# iot-gateway-usb-pd.net
KiCad netlist of a schematic drawn in EAGLE
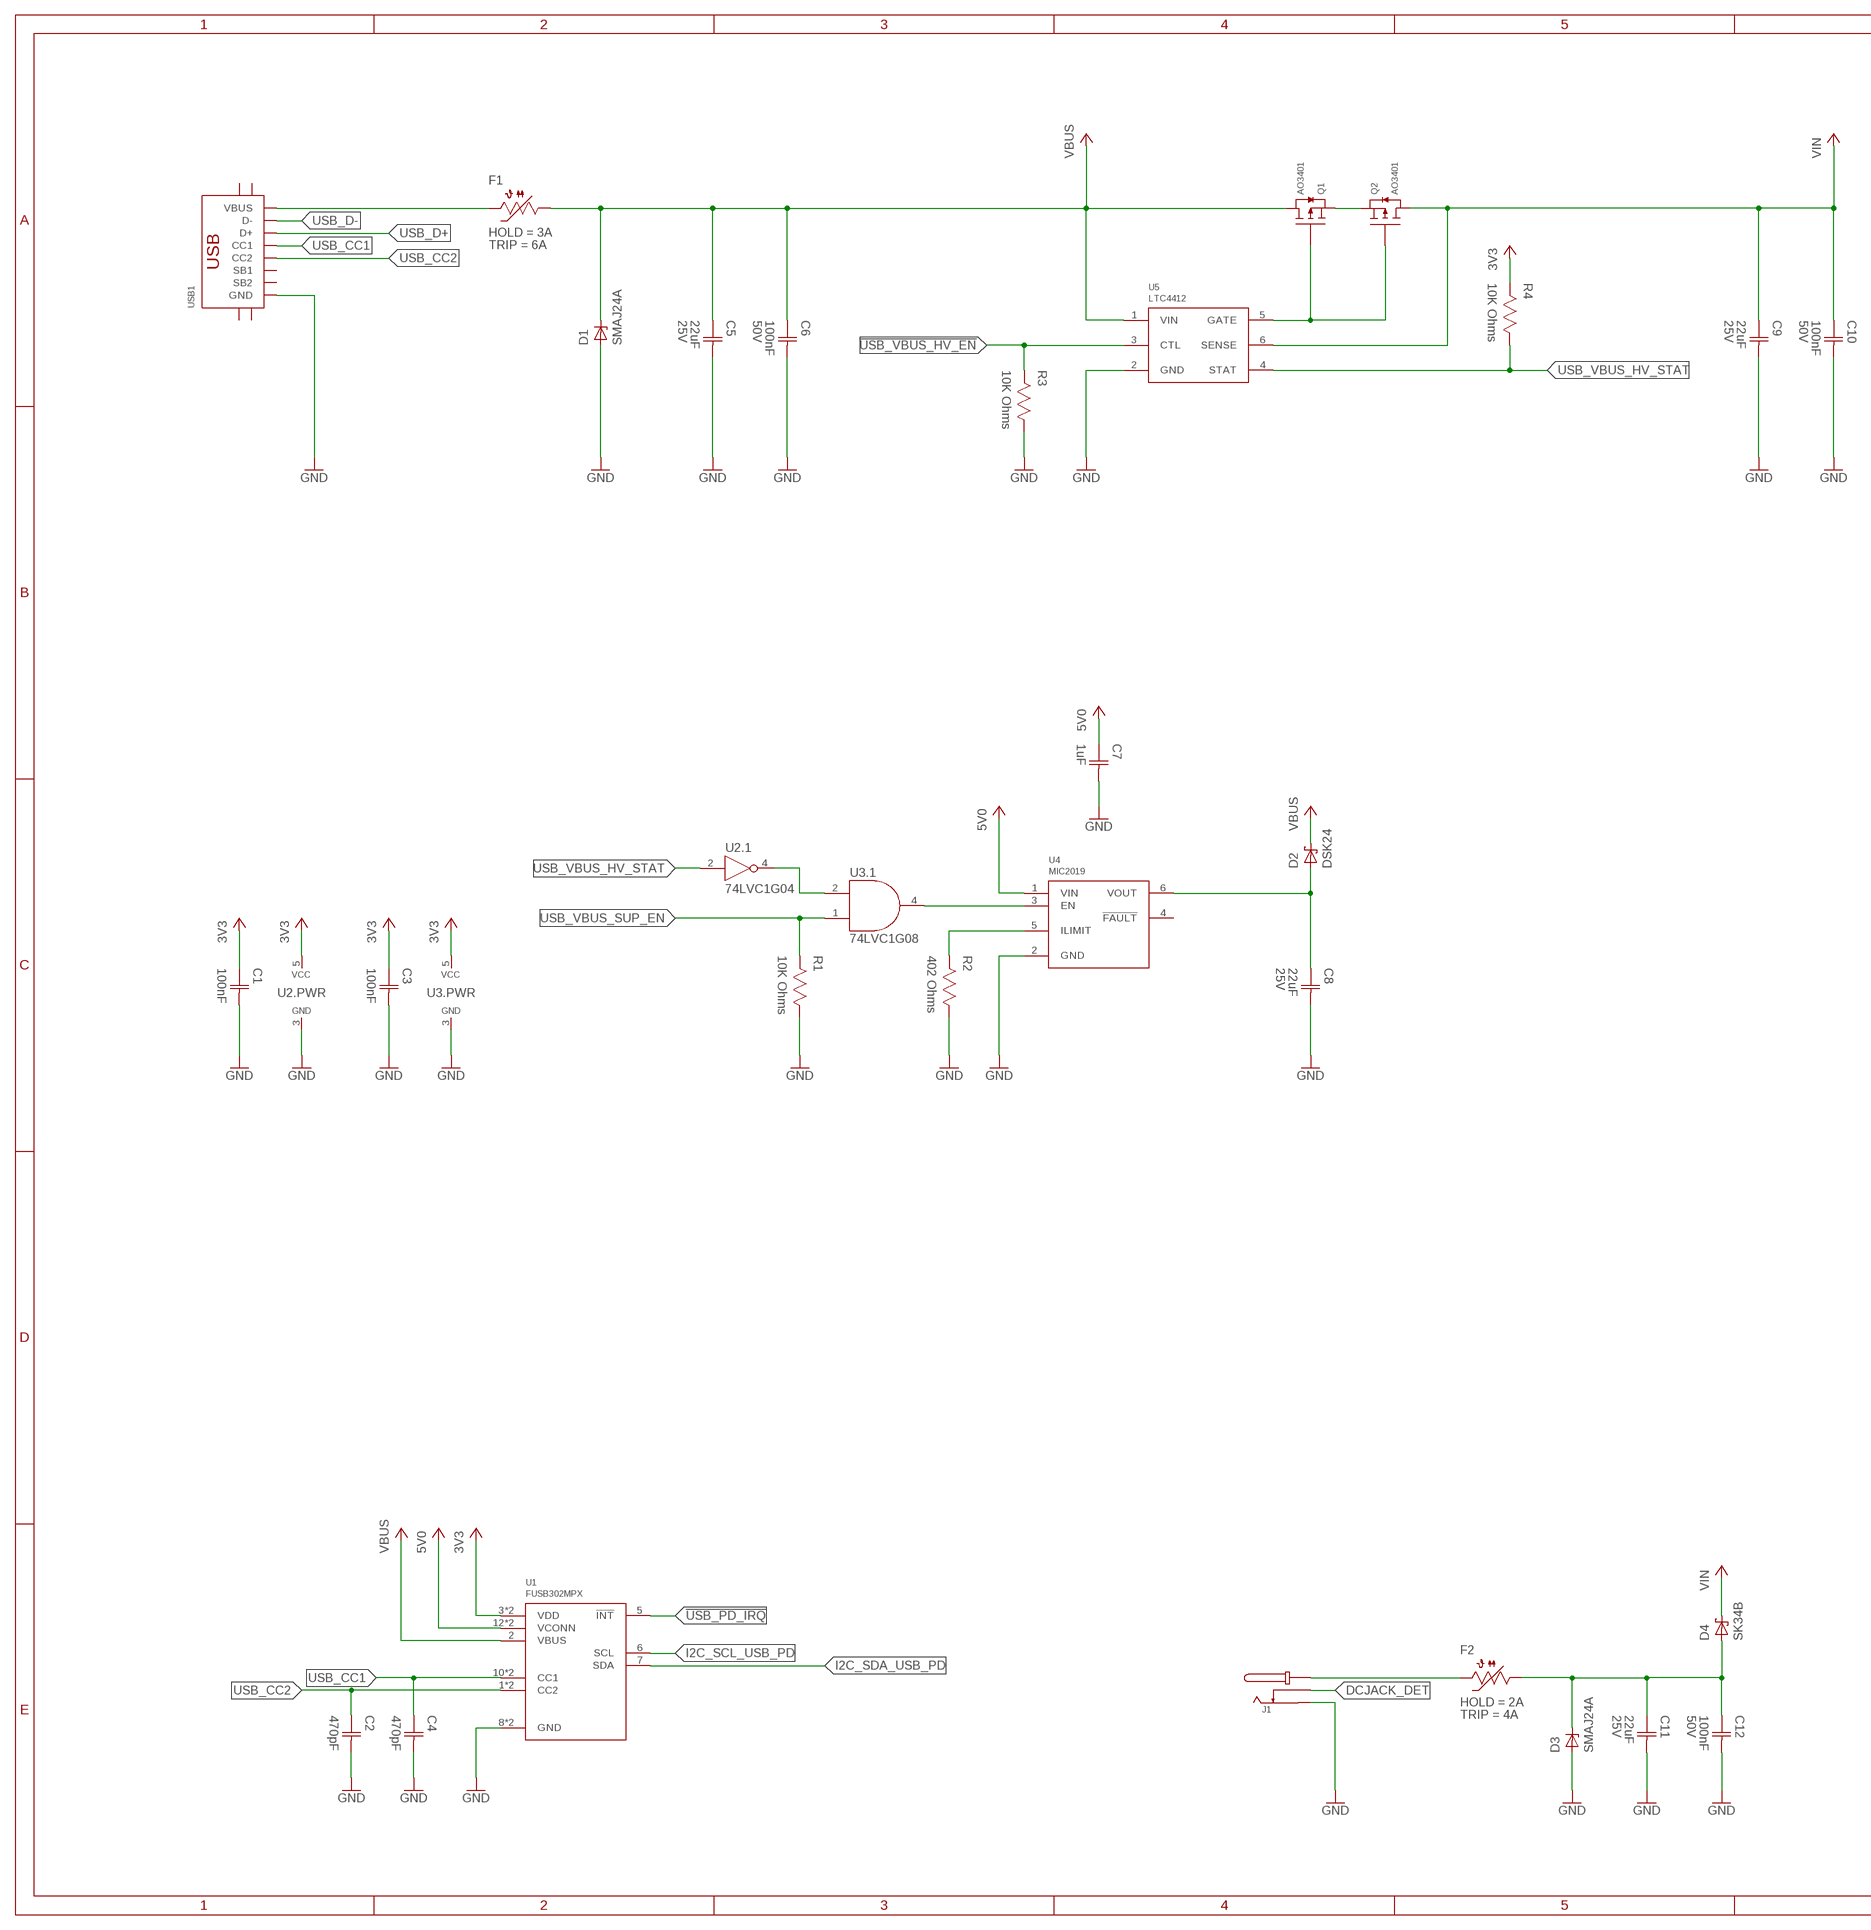
[diagram p0: schematic, sheet 1, part 1 of 2]
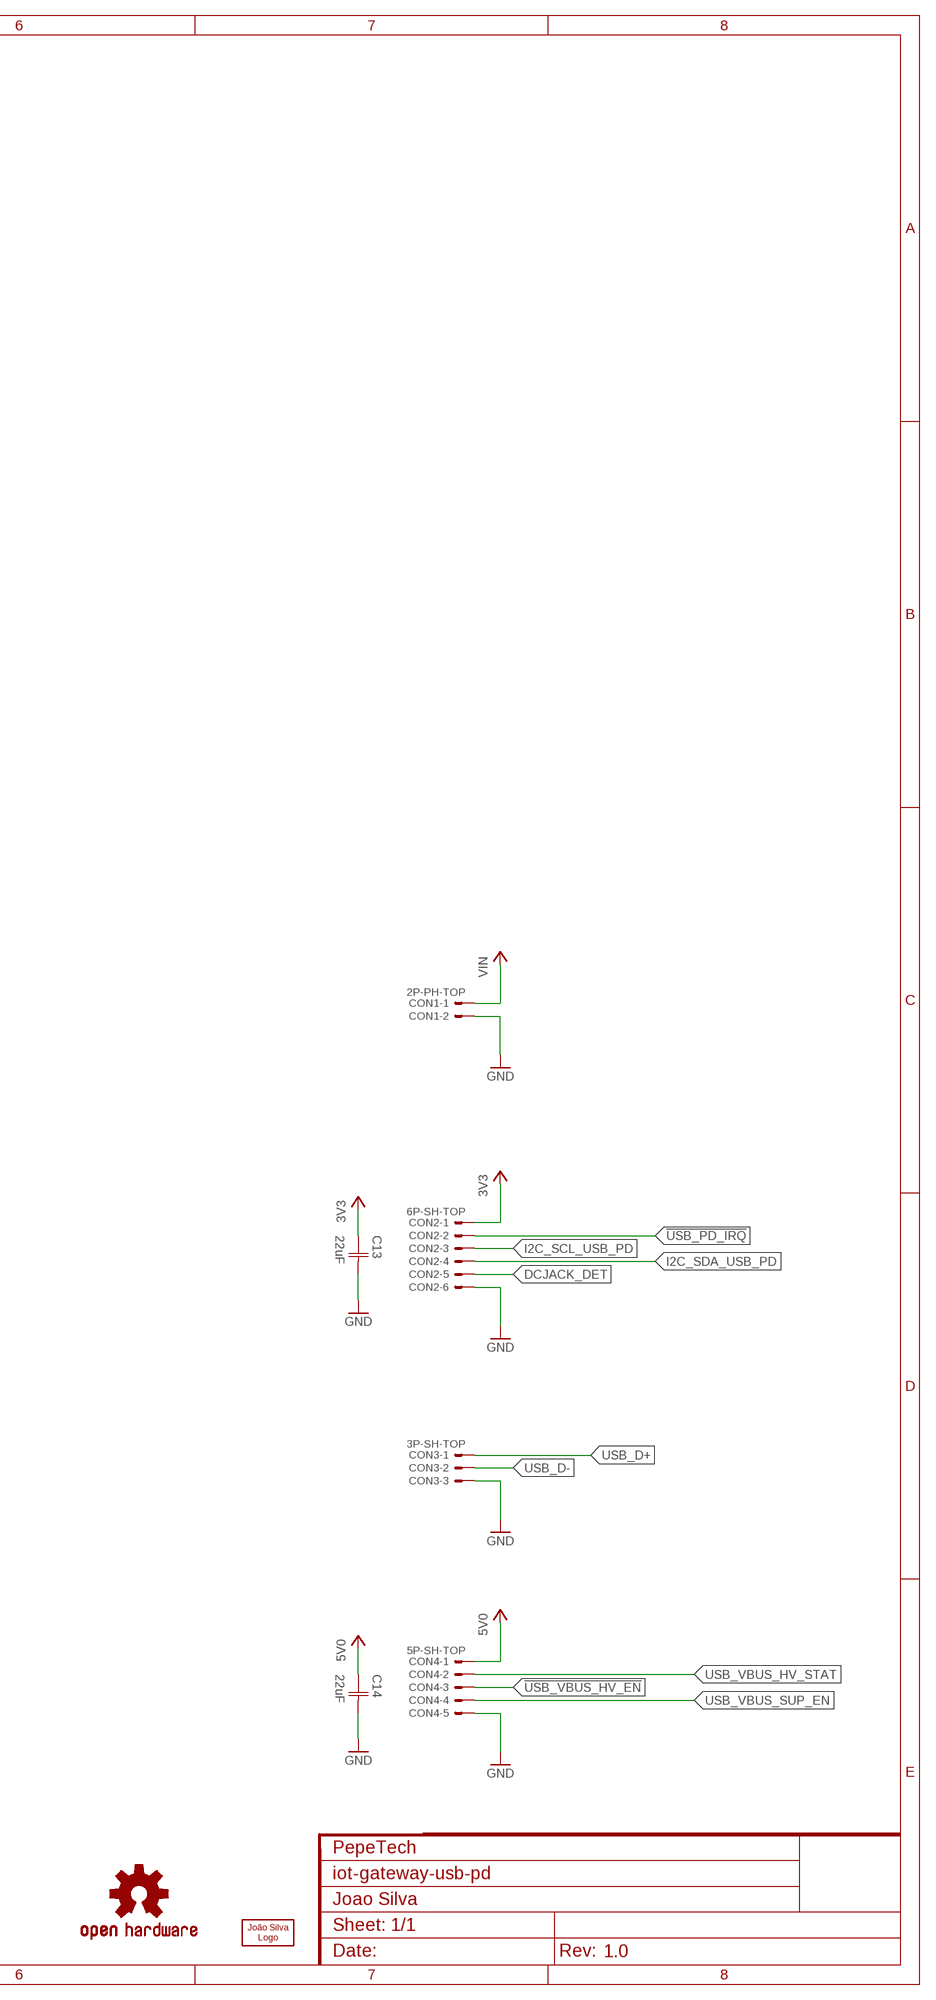
[diagram p1: schematic, sheet 1, part 2 of 2]

(export (version "E")
  (design (tool "Eeschema 10.0.6"))
  (components
    (comp (ref "C1")
      (value "100nF")
      (footprint "eagle-import:CAP0603")
      (libsource (lib "eagle-import") (part "CAPACITOR-0603"))
    )
    (comp (ref "C2")
      (value "470pF")
      (footprint "eagle-import:CAP0603")
      (libsource (lib "eagle-import") (part "CAPACITOR-0603"))
    )
    (comp (ref "C3")
      (value "100nF")
      (footprint "eagle-import:CAP0603")
      (libsource (lib "eagle-import") (part "CAPACITOR-0603"))
    )
    (comp (ref "C4")
      (value "470pF")
      (footprint "eagle-import:CAP0603")
      (libsource (lib "eagle-import") (part "CAPACITOR-0603"))
    )
    (comp (ref "C5")
      (value "22uF")
      (footprint "eagle-import:CAP1206")
      (fields (field (name "VOLTAGE") "25V"))
      (libsource (lib "eagle-import") (part "CAPACITOR-1206"))
    )
    (comp (ref "C6")
      (value "100nF")
      (footprint "eagle-import:CAP0603")
      (fields (field (name "VOLTAGE") "50V"))
      (libsource (lib "eagle-import") (part "CAPACITOR-0603"))
    )
    (comp (ref "C7")
      (value "1uF")
      (footprint "eagle-import:CAP0603")
      (libsource (lib "eagle-import") (part "CAPACITOR-0603"))
    )
    (comp (ref "C8")
      (value "22uF")
      (footprint "eagle-import:CAP1206")
      (fields (field (name "VOLTAGE") "25V"))
      (libsource (lib "eagle-import") (part "CAPACITOR-1206"))
    )
    (comp (ref "C9")
      (value "22uF")
      (footprint "eagle-import:CAP1206")
      (fields (field (name "VOLTAGE") "25V"))
      (libsource (lib "eagle-import") (part "CAPACITOR-1206"))
    )
    (comp (ref "C10")
      (value "100nF")
      (footprint "eagle-import:CAP0603")
      (fields (field (name "VOLTAGE") "50V"))
      (libsource (lib "eagle-import") (part "CAPACITOR-0603"))
    )
    (comp (ref "C11")
      (value "22uF")
      (footprint "eagle-import:CAP1206")
      (fields (field (name "VOLTAGE") "25V"))
      (libsource (lib "eagle-import") (part "CAPACITOR-1206"))
    )
    (comp (ref "C12")
      (value "100nF")
      (footprint "eagle-import:CAP0603")
      (fields (field (name "VOLTAGE") "50V"))
      (libsource (lib "eagle-import") (part "CAPACITOR-0603"))
    )
    (comp (ref "C13")
      (value "22uF")
      (footprint "eagle-import:CAP1206")
      (libsource (lib "eagle-import") (part "CAPACITOR-1206"))
    )
    (comp (ref "C14")
      (value "22uF")
      (footprint "eagle-import:CAP1206")
      (libsource (lib "eagle-import") (part "CAPACITOR-1206"))
    )
    (comp (ref "CON1")
      (value "2P-PH-TOP")
      (footprint "eagle-import:PH-02-TOP")
      (libsource (lib "eagle-import") (part "2P-PH-TOP"))
    )
    (comp (ref "CON2")
      (value "6P-SH-TOP")
      (footprint "eagle-import:SH-06-TOP")
      (libsource (lib "eagle-import") (part "6P-SH-TOP"))
    )
    (comp (ref "CON3")
      (value "3P-SH-TOP")
      (footprint "eagle-import:SH-03-TOP")
      (libsource (lib "eagle-import") (part "3P-SH-TOP"))
    )
    (comp (ref "CON4")
      (value "5P-SH-TOP")
      (footprint "eagle-import:SH-05-TOP")
      (libsource (lib "eagle-import") (part "5P-SH-TOP"))
    )
    (comp (ref "D1")
      (value "SMAJ24A")
      (footprint "eagle-import:DO214AC")
      (fields (field (name "MF") "Littelfuse"))
      (libsource (lib "eagle-import") (part "SMAJA24"))
    )
    (comp (ref "D2")
      (value "DSK24")
      (footprint "eagle-import:SOD-123F")
      (libsource (lib "eagle-import") (part "DSK24"))
    )
    (comp (ref "D3")
      (value "SMAJ24A")
      (footprint "eagle-import:DO214AC")
      (fields (field (name "MF") "Littelfuse"))
      (libsource (lib "eagle-import") (part "SMAJA24"))
    )
    (comp (ref "D4")
      (value "SK34B")
      (footprint "eagle-import:DO214AA")
      (libsource (lib "eagle-import") (part "SK34B"))
    )
    (comp (ref "F1")
      (value "PTC1206")
      (footprint "eagle-import:1206")
      (fields (field (name "HOLD") "3A") (field (name "TRIP") "6A"))
      (libsource (lib "eagle-import") (part "PTC1206"))
    )
    (comp (ref "F2")
      (value "PTC1206")
      (footprint "eagle-import:1206")
      (fields (field (name "HOLD") "2A") (field (name "TRIP") "4A"))
      (libsource (lib "eagle-import") (part "PTC1206"))
    )
    (comp (ref "J1")
      (value "DCJACK")
      (footprint "eagle-import:DC-050")
      (libsource (lib "eagle-import") (part "DCJACK"))
    )
    (comp (ref "LOGO1")
      (value "OSHW-LOGOS")
      (footprint "eagle-import:OSHW-LOGO-S")
      (libsource (lib "eagle-import") (part "OSHW-LOGOS"))
    )
    (comp (ref "LOGO2")
      (value "JS-5MM")
      (footprint "eagle-import:JS_5MM")
      (libsource (lib "eagle-import") (part "JS-5MM"))
    )
    (comp (ref "Q1")
      (value "AO3401")
      (footprint "eagle-import:SOT23")
      (libsource (lib "eagle-import") (part "AO3401"))
    )
    (comp (ref "Q2")
      (value "AO3401")
      (footprint "eagle-import:SOT23")
      (libsource (lib "eagle-import") (part "AO3401"))
    )
    (comp (ref "R1")
      (value "10K Ohms")
      (footprint "eagle-import:RES0603")
      (libsource (lib "eagle-import") (part "RESISTOR-0603"))
    )
    (comp (ref "R2")
      (value "402 Ohms")
      (footprint "eagle-import:RES0603")
      (libsource (lib "eagle-import") (part "RESISTOR-0603"))
    )
    (comp (ref "R3")
      (value "10K Ohms")
      (footprint "eagle-import:RES0603")
      (libsource (lib "eagle-import") (part "RESISTOR-0603"))
    )
    (comp (ref "R4")
      (value "10K Ohms")
      (footprint "eagle-import:RES0603")
      (libsource (lib "eagle-import") (part "RESISTOR-0603"))
    )
    (comp (ref "U1")
      (value "FUSB302MPX")
      (footprint "eagle-import:QFN14")
      (libsource (lib "eagle-import") (part "FUSB302MPX"))
    )
    (comp (ref "U2")
      (value "74LVC1G04")
      (footprint "eagle-import:SC70-5")
      (libsource (lib "eagle-import") (part "74LVC1G04"))
    )
    (comp (ref "U3")
      (value "74LVC1G08")
      (footprint "eagle-import:SC70-5")
      (libsource (lib "eagle-import") (part "74LVC1G08"))
    )
    (comp (ref "U4")
      (value "MIC2019")
      (footprint "eagle-import:SOT23-6")
      (libsource (lib "eagle-import") (part "MIC2091"))
    )
    (comp (ref "U5")
      (value "LTC4412")
      (footprint "eagle-import:SOT23-6")
      (libsource (lib "eagle-import") (part "LTC4412"))
    )
    (comp (ref "USB1")
      (value "USB-C-16P-SMD-FLAT-SIDE-TYPE-2")
      (footprint "eagle-import:USB-C-16P-SMD-FLAT-SIDE-TYPE-2")
      (libsource (lib "eagle-import") (part "USB-C-16P-SMD-FLAT-SIDE-TYPE-2"))
    )
  )
  (nets
    (net (code "1") (name "/~{USB_PD_IRQ}") (class "Default")
      (node (ref "CON2") (pin "2") (pinfunction "S_2") (pintype "passive"))
      (node (ref "U1") (pin "5") (pinfunction "~{INT}_5") (pintype "bidirectional"))
    )
    (net (code "2") (name "/~{USB_VBUS_HV_EN}") (class "Default")
      (node (ref "CON4") (pin "3") (pinfunction "S_3") (pintype "passive"))
      (node (ref "R3") (pin "2") (pinfunction "2_2") (pintype "passive"))
      (node (ref "U5") (pin "3") (pinfunction "CTL_3") (pintype "bidirectional"))
    )
    (net (code "3") (name "3V3") (class "Default")
      (node (ref "C1") (pin "1") (pinfunction "C1_1") (pintype "passive"))
      (node (ref "C13") (pin "1") (pinfunction "C1_1") (pintype "passive"))
      (node (ref "C3") (pin "1") (pinfunction "C1_1") (pintype "passive"))
      (node (ref "CON2") (pin "1") (pinfunction "S_1") (pintype "passive"))
      (node (ref "R4") (pin "2") (pinfunction "2_2") (pintype "passive"))
      (node (ref "U1") (pin "3") (pinfunction "VDD_3") (pintype "bidirectional"))
      (node (ref "U1") (pin "4") (pinfunction "VDD_4") (pintype "bidirectional"))
      (node (ref "U2") (pin "5") (pinfunction "VCC_5") (pintype "power_in"))
      (node (ref "U3") (pin "5") (pinfunction "VCC_5") (pintype "power_in"))
    )
    (net (code "4") (name "5V0") (class "Default")
      (node (ref "C14") (pin "1") (pinfunction "C1_1") (pintype "passive"))
      (node (ref "C7") (pin "1") (pinfunction "C1_1") (pintype "passive"))
      (node (ref "CON4") (pin "1") (pinfunction "S_1") (pintype "passive"))
      (node (ref "U1") (pin "12") (pinfunction "VCONN_12") (pintype "bidirectional"))
      (node (ref "U1") (pin "13") (pinfunction "VCONN_13") (pintype "bidirectional"))
      (node (ref "U4") (pin "1") (pinfunction "VIN_1") (pintype "bidirectional"))
    )
    (net (code "5") (name "DCJACK_DET") (class "Default")
      (node (ref "CON2") (pin "5") (pinfunction "S_5") (pintype "passive"))
      (node (ref "J1") (pin "DT") (pinfunction "DT_DT") (pintype "bidirectional"))
    )
    (net (code "6") (name "GND") (class "Default")
      (node (ref "C1") (pin "2") (pinfunction "C2_2") (pintype "passive"))
      (node (ref "C10") (pin "2") (pinfunction "C2_2") (pintype "passive"))
      (node (ref "C11") (pin "2") (pinfunction "C2_2") (pintype "passive"))
      (node (ref "C12") (pin "2") (pinfunction "C2_2") (pintype "passive"))
      (node (ref "C13") (pin "2") (pinfunction "C2_2") (pintype "passive"))
      (node (ref "C14") (pin "2") (pinfunction "C2_2") (pintype "passive"))
      (node (ref "C2") (pin "2") (pinfunction "C2_2") (pintype "passive"))
      (node (ref "C3") (pin "2") (pinfunction "C2_2") (pintype "passive"))
      (node (ref "C4") (pin "2") (pinfunction "C2_2") (pintype "passive"))
      (node (ref "C5") (pin "2") (pinfunction "C2_2") (pintype "passive"))
      (node (ref "C6") (pin "2") (pinfunction "C2_2") (pintype "passive"))
      (node (ref "C7") (pin "2") (pinfunction "C2_2") (pintype "passive"))
      (node (ref "C8") (pin "2") (pinfunction "C2_2") (pintype "passive"))
      (node (ref "C9") (pin "2") (pinfunction "C2_2") (pintype "passive"))
      (node (ref "CON1") (pin "2") (pinfunction "S_2") (pintype "passive"))
      (node (ref "CON2") (pin "6") (pinfunction "S_6") (pintype "passive"))
      (node (ref "CON3") (pin "3") (pinfunction "S_3") (pintype "passive"))
      (node (ref "CON4") (pin "5") (pinfunction "S_5") (pintype "passive"))
      (node (ref "D1") (pin "A") (pinfunction "A_A") (pintype "passive"))
      (node (ref "D3") (pin "A") (pinfunction "A_A") (pintype "passive"))
      (node (ref "J1") (pin "O") (pinfunction "O_O") (pintype "bidirectional"))
      (node (ref "R1") (pin "1") (pinfunction "1_1") (pintype "passive"))
      (node (ref "R2") (pin "1") (pinfunction "1_1") (pintype "passive"))
      (node (ref "R3") (pin "1") (pinfunction "1_1") (pintype "passive"))
      (node (ref "U1") (pin "8") (pinfunction "GND_8") (pintype "bidirectional"))
      (node (ref "U1") (pin "9") (pinfunction "GND_9") (pintype "bidirectional"))
      (node (ref "U2") (pin "3") (pinfunction "GND_3") (pintype "power_in"))
      (node (ref "U3") (pin "3") (pinfunction "GND_3") (pintype "power_in"))
      (node (ref "U4") (pin "2") (pinfunction "GND_2") (pintype "bidirectional"))
      (node (ref "U5") (pin "2") (pinfunction "GND_2") (pintype "bidirectional"))
      (node (ref "USB1") (pin "A1/B12") (pinfunction "GND_A1/B12") (pintype "bidirectional"))
      (node (ref "USB1") (pin "B1/A12") (pinfunction "GND_B1/A12") (pintype "bidirectional"))
    )
    (net (code "7") (name "I2C_SCL_USB_PD") (class "Default")
      (node (ref "CON2") (pin "3") (pinfunction "S_3") (pintype "passive"))
      (node (ref "U1") (pin "6") (pinfunction "SCL_6") (pintype "bidirectional"))
    )
    (net (code "8") (name "I2C_SDA_USB_PD") (class "Default")
      (node (ref "CON2") (pin "4") (pinfunction "S_4") (pintype "passive"))
      (node (ref "U1") (pin "7") (pinfunction "SDA_7") (pintype "bidirectional"))
    )
    (net (code "9") (name "Net-(C8-C1)") (class "Default")
      (node (ref "C8") (pin "1") (pinfunction "C1_1") (pintype "passive"))
      (node (ref "D2") (pin "A") (pinfunction "A_A") (pintype "passive"))
      (node (ref "U4") (pin "6") (pinfunction "VOUT_6") (pintype "bidirectional"))
    )
    (net (code "10") (name "Net-(C11-C1)") (class "Default")
      (node (ref "C11") (pin "1") (pinfunction "C1_1") (pintype "passive"))
      (node (ref "C12") (pin "1") (pinfunction "C1_1") (pintype "passive"))
      (node (ref "D3") (pin "C") (pinfunction "C_C") (pintype "passive"))
      (node (ref "D4") (pin "A") (pinfunction "A_A") (pintype "passive"))
      (node (ref "F2") (pin "1") (pinfunction "1_1") (pintype "passive"))
    )
    (net (code "11") (name "Net-(F1-Pad2)") (class "Default")
      (node (ref "F1") (pin "2") (pinfunction "2_2") (pintype "passive"))
      (node (ref "USB1") (pin "A4/B9") (pinfunction "VBUS_A4/B9") (pintype "bidirectional"))
      (node (ref "USB1") (pin "B4/A9") (pinfunction "VBUS_B4/A9") (pintype "bidirectional"))
    )
    (net (code "12") (name "Net-(F2-Pad2)") (class "Default")
      (node (ref "F2") (pin "2") (pinfunction "2_2") (pintype "passive"))
      (node (ref "J1") (pin "C") (pinfunction "C_C") (pintype "bidirectional"))
      (node (ref "J1") (pin "C'") (pinfunction "C_C'") (pintype "bidirectional"))
    )
    (net (code "13") (name "Net-(Q1-G)") (class "Default")
      (node (ref "Q1") (pin "1") (pinfunction "G_1") (pintype "passive"))
      (node (ref "Q2") (pin "1") (pinfunction "G_1") (pintype "passive"))
      (node (ref "U5") (pin "5") (pinfunction "GATE_5") (pintype "bidirectional"))
    )
    (net (code "14") (name "Net-(Q1-S)") (class "Default")
      (node (ref "Q1") (pin "2") (pinfunction "S_2") (pintype "passive"))
      (node (ref "Q2") (pin "2") (pinfunction "S_2") (pintype "passive"))
    )
    (net (code "15") (name "Net-(U2A-Y)") (class "Default")
      (node (ref "U2") (pin "4") (pinfunction "Y_4") (pintype "output"))
      (node (ref "U3") (pin "2") (pinfunction "A_2") (pintype "input"))
    )
    (net (code "16") (name "Net-(U3A-Y)") (class "Default")
      (node (ref "U3") (pin "4") (pinfunction "Y_4") (pintype "output"))
      (node (ref "U4") (pin "3") (pinfunction "EN_3") (pintype "bidirectional"))
    )
    (net (code "17") (name "Net-(U4-ILIMIT)") (class "Default")
      (node (ref "R2") (pin "2") (pinfunction "2_2") (pintype "passive"))
      (node (ref "U4") (pin "5") (pinfunction "ILIMIT_5") (pintype "bidirectional"))
    )
    (net (code "18") (name "USB_CC1") (class "Default")
      (node (ref "C4") (pin "1") (pinfunction "C1_1") (pintype "passive"))
      (node (ref "U1") (pin "10") (pinfunction "CC1_10") (pintype "bidirectional"))
      (node (ref "U1") (pin "11") (pinfunction "CC1_11") (pintype "bidirectional"))
      (node (ref "USB1") (pin "A5") (pinfunction "CC1_A5") (pintype "bidirectional"))
    )
    (net (code "19") (name "USB_CC2") (class "Default")
      (node (ref "C2") (pin "1") (pinfunction "C1_1") (pintype "passive"))
      (node (ref "U1") (pin "1") (pinfunction "CC2_1") (pintype "bidirectional"))
      (node (ref "U1") (pin "14") (pinfunction "CC2_14") (pintype "bidirectional"))
      (node (ref "USB1") (pin "B5") (pinfunction "CC2_B5") (pintype "bidirectional"))
    )
    (net (code "20") (name "USB_D+") (class "Default")
      (node (ref "CON3") (pin "1") (pinfunction "S_1") (pintype "passive"))
      (node (ref "USB1") (pin "A6") (pinfunction "D+_A6") (pintype "bidirectional"))
      (node (ref "USB1") (pin "B6") (pinfunction "D+_B6") (pintype "bidirectional"))
    )
    (net (code "21") (name "USB_D-") (class "Default")
      (node (ref "CON3") (pin "2") (pinfunction "S_2") (pintype "passive"))
      (node (ref "USB1") (pin "A7") (pinfunction "D-_A7") (pintype "bidirectional"))
      (node (ref "USB1") (pin "B7") (pinfunction "D-_B7") (pintype "bidirectional"))
    )
    (net (code "22") (name "USB_VBUS_HV_STAT") (class "Default")
      (node (ref "CON4") (pin "2") (pinfunction "S_2") (pintype "passive"))
      (node (ref "R4") (pin "1") (pinfunction "1_1") (pintype "passive"))
      (node (ref "U2") (pin "2") (pinfunction "A_2") (pintype "input"))
      (node (ref "U5") (pin "4") (pinfunction "STAT_4") (pintype "bidirectional"))
    )
    (net (code "23") (name "USB_VBUS_SUP_EN") (class "Default")
      (node (ref "CON4") (pin "4") (pinfunction "S_4") (pintype "passive"))
      (node (ref "R1") (pin "2") (pinfunction "2_2") (pintype "passive"))
      (node (ref "U3") (pin "1") (pinfunction "B_1") (pintype "input"))
    )
    (net (code "24") (name "VBUS") (class "Default")
      (node (ref "C5") (pin "1") (pinfunction "C1_1") (pintype "passive"))
      (node (ref "C6") (pin "1") (pinfunction "C1_1") (pintype "passive"))
      (node (ref "D1") (pin "C") (pinfunction "C_C") (pintype "passive"))
      (node (ref "D2") (pin "C") (pinfunction "C_C") (pintype "passive"))
      (node (ref "F1") (pin "1") (pinfunction "1_1") (pintype "passive"))
      (node (ref "Q1") (pin "3") (pinfunction "D_3") (pintype "passive"))
      (node (ref "U1") (pin "2") (pinfunction "VBUS_2") (pintype "bidirectional"))
      (node (ref "U5") (pin "1") (pinfunction "VIN_1") (pintype "bidirectional"))
    )
    (net (code "25") (name "VIN") (class "Default")
      (node (ref "C10") (pin "1") (pinfunction "C1_1") (pintype "passive"))
      (node (ref "C9") (pin "1") (pinfunction "C1_1") (pintype "passive"))
      (node (ref "CON1") (pin "1") (pinfunction "S_1") (pintype "passive"))
      (node (ref "D4") (pin "C") (pinfunction "C_C") (pintype "passive"))
      (node (ref "Q2") (pin "3") (pinfunction "D_3") (pintype "passive"))
      (node (ref "U5") (pin "6") (pinfunction "SENSE_6") (pintype "bidirectional"))
    )
    (net (code "26") (name "unconnected-(U4-~{FAULT}-Pad4)") (class "Default")
      (node (ref "U4") (pin "4") (pinfunction "~{FAULT}_4") (pintype "bidirectional"))
    )
    (net (code "27") (name "unconnected-(USB1-SB1-PadA8)") (class "Default")
      (node (ref "USB1") (pin "A8") (pinfunction "SB1_A8") (pintype "bidirectional"))
    )
    (net (code "28") (name "unconnected-(USB1-SB2-PadB8)") (class "Default")
      (node (ref "USB1") (pin "B8") (pinfunction "SB2_B8") (pintype "bidirectional"))
    )
    (net (code "29") (name "unconnected-(USB1-SHIELD-PadSHIELD@0)") (class "Default")
      (node (ref "USB1") (pin "SHIELD@0") (pinfunction "SHIELD_SHIELD@0") (pintype "bidirectional"))
    )
    (net (code "30") (name "unconnected-(USB1-SHIELD-PadSHIELD@1)") (class "Default")
      (node (ref "USB1") (pin "SHIELD@1") (pinfunction "SHIELD_SHIELD@1") (pintype "bidirectional"))
    )
    (net (code "31") (name "unconnected-(USB1-SHIELD-PadSHIELD@2)") (class "Default")
      (node (ref "USB1") (pin "SHIELD@2") (pinfunction "SHIELD_SHIELD@2") (pintype "bidirectional"))
    )
    (net (code "32") (name "unconnected-(USB1-SHIELD-PadSHIELD@3)") (class "Default")
      (node (ref "USB1") (pin "SHIELD@3") (pinfunction "SHIELD_SHIELD@3") (pintype "bidirectional"))
    )
  )
)
